# Fri3d_2026_DJ_01.net
KiCad netlist of a schematic drawn in Altium Designer
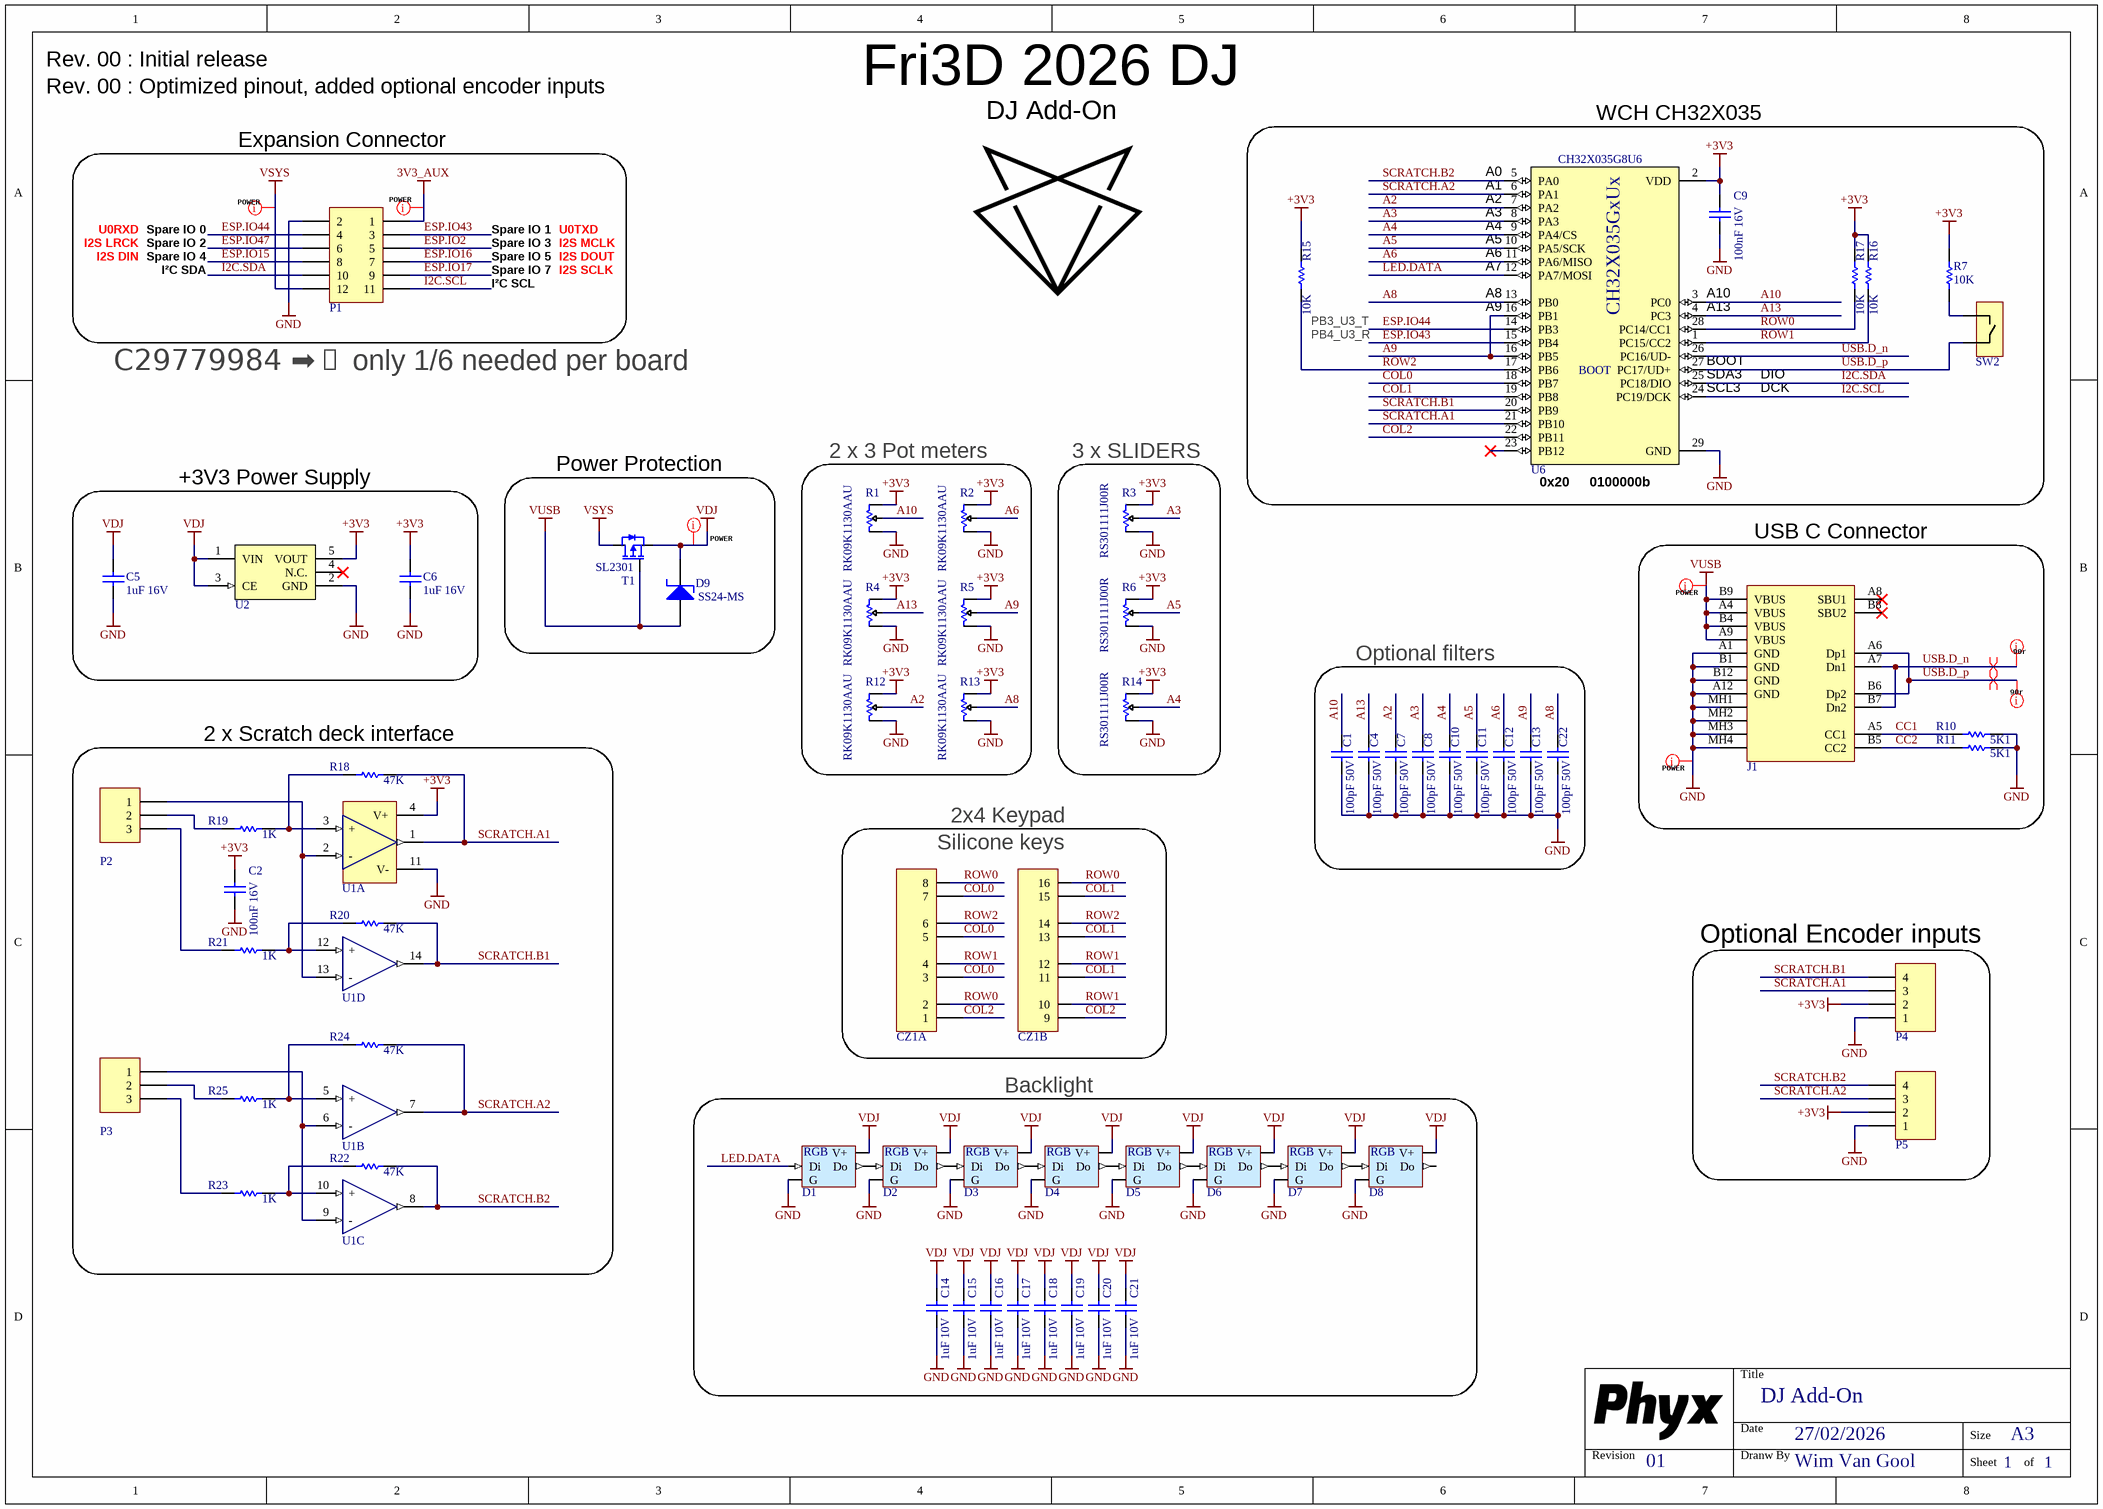
[diagram p0: Fri3d_2026_DJ_01.SchDoc]

(export (version "E")
  (design (tool "Eeschema 10.0.6"))
  (components
    (comp (ref "C1")
      (value "100pF 50V")
      (footprint "C0603_N")
      (description "Capacitor Ceramic")
      (libsource (lib "Phyx_Components") (part "CAP_CERAMIC"))
    )
    (comp (ref "C2")
      (value "100nF 16V")
      (footprint "C0603_N")
      (description "Capacitor Ceramic")
      (libsource (lib "Phyx_Components") (part "CAP_CERAMIC"))
    )
    (comp (ref "C4")
      (value "100pF 50V")
      (footprint "C0603_N")
      (description "Capacitor Ceramic")
      (libsource (lib "Phyx_Components") (part "CAP_CERAMIC"))
    )
    (comp (ref "C5")
      (value "1uF 16V")
      (footprint "C0603_N")
      (description "Capacitor Ceramic")
      (libsource (lib "Phyx_Components") (part "CAP_CERAMIC"))
    )
    (comp (ref "C6")
      (value "1uF 16V")
      (footprint "C0603_N")
      (description "Capacitor Ceramic")
      (libsource (lib "Phyx_Components") (part "CAP_CERAMIC"))
    )
    (comp (ref "C7")
      (value "100pF 50V")
      (footprint "C0603_N")
      (description "Capacitor Ceramic")
      (libsource (lib "Phyx_Components") (part "CAP_CERAMIC"))
    )
    (comp (ref "C8")
      (value "100pF 50V")
      (footprint "C0603_N")
      (description "Capacitor Ceramic")
      (libsource (lib "Phyx_Components") (part "CAP_CERAMIC"))
    )
    (comp (ref "C9")
      (value "100nF 16V")
      (footprint "C0603_N")
      (description "Capacitor Ceramic")
      (libsource (lib "Phyx_Components") (part "CAP_CERAMIC"))
    )
    (comp (ref "C10")
      (value "100pF 50V")
      (footprint "C0603_N")
      (description "Capacitor Ceramic")
      (libsource (lib "Phyx_Components") (part "CAP_CERAMIC"))
    )
    (comp (ref "C11")
      (value "100pF 50V")
      (footprint "C0603_N")
      (description "Capacitor Ceramic")
      (libsource (lib "Phyx_Components") (part "CAP_CERAMIC"))
    )
    (comp (ref "C12")
      (value "100pF 50V")
      (footprint "C0603_N")
      (description "Capacitor Ceramic")
      (libsource (lib "Phyx_Components") (part "CAP_CERAMIC"))
    )
    (comp (ref "C13")
      (value "100pF 50V")
      (footprint "C0603_N")
      (description "Capacitor Ceramic")
      (libsource (lib "Phyx_Components") (part "CAP_CERAMIC"))
    )
    (comp (ref "C14")
      (value "1uF 10V")
      (footprint "C0402")
      (description "Capacitor Ceramic")
      (libsource (lib "Phyx_Components") (part "CAP_CERAMIC"))
    )
    (comp (ref "C15")
      (value "1uF 10V")
      (footprint "C0402")
      (description "Capacitor Ceramic")
      (libsource (lib "Phyx_Components") (part "CAP_CERAMIC"))
    )
    (comp (ref "C16")
      (value "1uF 10V")
      (footprint "C0402")
      (description "Capacitor Ceramic")
      (libsource (lib "Phyx_Components") (part "CAP_CERAMIC"))
    )
    (comp (ref "C17")
      (value "1uF 10V")
      (footprint "C0402")
      (description "Capacitor Ceramic")
      (libsource (lib "Phyx_Components") (part "CAP_CERAMIC"))
    )
    (comp (ref "C18")
      (value "1uF 10V")
      (footprint "C0402")
      (description "Capacitor Ceramic")
      (libsource (lib "Phyx_Components") (part "CAP_CERAMIC"))
    )
    (comp (ref "C19")
      (value "1uF 10V")
      (footprint "C0402")
      (description "Capacitor Ceramic")
      (libsource (lib "Phyx_Components") (part "CAP_CERAMIC"))
    )
    (comp (ref "C20")
      (value "1uF 10V")
      (footprint "C0402")
      (description "Capacitor Ceramic")
      (libsource (lib "Phyx_Components") (part "CAP_CERAMIC"))
    )
    (comp (ref "C21")
      (value "1uF 10V")
      (footprint "C0402")
      (description "Capacitor Ceramic")
      (libsource (lib "Phyx_Components") (part "CAP_CERAMIC"))
    )
    (comp (ref "C22")
      (value "100pF 50V")
      (footprint "C0603_N")
      (description "Capacitor Ceramic")
      (libsource (lib "Phyx_Components") (part "CAP_CERAMIC"))
    )
    (comp (ref "CZ1")
      (value "Campzone 2020 2x4 silicone keypad")
      (footprint "CZ20_2x4")
      (libsource (lib "Phyx_Components") (part "CZ20_2x4"))
    )
    (comp (ref "D1")
      (value "WS2812 based digital RGB LED 5050 White package reduced current")
      (footprint "LED_5050_WS2812B_WHITE")
      (description "=Description")
      (libsource (lib "Phyx_Components") (part "LED_RGB_WS2812B_5050"))
    )
    (comp (ref "D2")
      (value "WS2812 based digital RGB LED 5050 White package reduced current")
      (footprint "LED_5050_WS2812B_WHITE")
      (description "=Description")
      (libsource (lib "Phyx_Components") (part "LED_RGB_WS2812B_5050"))
    )
    (comp (ref "D3")
      (value "WS2812 based digital RGB LED 5050 White package reduced current")
      (footprint "LED_5050_WS2812B_WHITE")
      (description "=Description")
      (libsource (lib "Phyx_Components") (part "LED_RGB_WS2812B_5050"))
    )
    (comp (ref "D4")
      (value "WS2812 based digital RGB LED 5050 White package reduced current")
      (footprint "LED_5050_WS2812B_WHITE")
      (description "=Description")
      (libsource (lib "Phyx_Components") (part "LED_RGB_WS2812B_5050"))
    )
    (comp (ref "D5")
      (value "WS2812 based digital RGB LED 5050 White package reduced current")
      (footprint "LED_5050_WS2812B_WHITE")
      (description "=Description")
      (libsource (lib "Phyx_Components") (part "LED_RGB_WS2812B_5050"))
    )
    (comp (ref "D6")
      (value "WS2812 based digital RGB LED 5050 White package reduced current")
      (footprint "LED_5050_WS2812B_WHITE")
      (description "=Description")
      (libsource (lib "Phyx_Components") (part "LED_RGB_WS2812B_5050"))
    )
    (comp (ref "D7")
      (value "WS2812 based digital RGB LED 5050 White package reduced current")
      (footprint "LED_5050_WS2812B_WHITE")
      (description "=Description")
      (libsource (lib "Phyx_Components") (part "LED_RGB_WS2812B_5050"))
    )
    (comp (ref "D8")
      (value "WS2812 based digital RGB LED 5050 White package reduced current")
      (footprint "LED_5050_WS2812B_WHITE")
      (description "=Description")
      (libsource (lib "Phyx_Components") (part "LED_RGB_WS2812B_5050"))
    )
    (comp (ref "D9")
      (value "SS24-MS")
      (footprint "DO-214AC_AC")
      (description "=Description")
      (fields (field (name "Comment") "40V 2A 550mV@2A DO-214 Schottky"))
      (libsource (lib "Phyx_Components") (part "Schottky_AC"))
    )
    (comp (ref "J1")
      (value "USB 2.0 C Reversible Receptacle Horizontal full SMD")
      (footprint "XUNPU-TYPEC-304S-ACP16")
      (libsource (lib "Phyx_Components") (part "USB_C_16_4"))
    )
    (comp (ref "P1")
      (value "Header 6X2")
      (footprint "HDR2X6")
      (libsource (lib "Phyx_Components") (part "Header 6X2"))
    )
    (comp (ref "P2")
      (value "Header 3")
      (footprint "HDR1X3")
      (libsource (lib "Phyx_Components") (part "Header 3"))
    )
    (comp (ref "P3")
      (value "Header 3")
      (footprint "HDR1X3")
      (libsource (lib "Phyx_Components") (part "Header 3"))
    )
    (comp (ref "P4")
      (value "Header 1.0mm RA Shrouded 4")
      (footprint "WE_665104131822")
      (libsource (lib "Phyx_Components") (part "Header 4"))
    )
    (comp (ref "P5")
      (value "Header 1.0mm RA Shrouded 4")
      (footprint "WE_665104131822")
      (libsource (lib "Phyx_Components") (part "Header 4"))
    )
    (comp (ref "R1")
      (value "RK09K1130AAU")
      (footprint "ALPS_RK09K1130AAU")
      (fields (field (name "Comment") "10kΩ Rotary Potentiometers"))
      (libsource (lib "Phyx_Components") (part "RES_VAR"))
    )
    (comp (ref "R2")
      (value "RK09K1130AAU")
      (footprint "ALPS_RK09K1130AAU")
      (fields (field (name "Comment") "10kΩ Rotary Potentiometers"))
      (libsource (lib "Phyx_Components") (part "RES_VAR"))
    )
    (comp (ref "R3")
      (value "RS301111J00R")
      (footprint "ALPS_RS301111J00R")
      (fields (field (name "Comment") "50kΩ Slide Potentiometers"))
      (libsource (lib "Phyx_Components") (part "RES_VAR"))
    )
    (comp (ref "R4")
      (value "RK09K1130AAU")
      (footprint "ALPS_RK09K1130AAU")
      (fields (field (name "Comment") "10kΩ Rotary Potentiometers"))
      (libsource (lib "Phyx_Components") (part "RES_VAR"))
    )
    (comp (ref "R5")
      (value "RK09K1130AAU")
      (footprint "ALPS_RK09K1130AAU")
      (fields (field (name "Comment") "10kΩ Rotary Potentiometers"))
      (libsource (lib "Phyx_Components") (part "RES_VAR"))
    )
    (comp (ref "R6")
      (value "RS301111J00R")
      (footprint "ALPS_RS301111J00R")
      (fields (field (name "Comment") "50kΩ Slide Potentiometers"))
      (libsource (lib "Phyx_Components") (part "RES_VAR"))
    )
    (comp (ref "R7")
      (value "10K")
      (footprint "R0603_N")
      (libsource (lib "Phyx_Components") (part "RESISTOR"))
    )
    (comp (ref "R10")
      (value "5K1")
      (footprint "R0603_N")
      (libsource (lib "Phyx_Components") (part "RESISTOR"))
    )
    (comp (ref "R11")
      (value "5K1")
      (footprint "R0603_N")
      (libsource (lib "Phyx_Components") (part "RESISTOR"))
    )
    (comp (ref "R12")
      (value "RK09K1130AAU")
      (footprint "ALPS_RK09K1130AAU")
      (fields (field (name "Comment") "10kΩ Rotary Potentiometers"))
      (libsource (lib "Phyx_Components") (part "RES_VAR"))
    )
    (comp (ref "R13")
      (value "RK09K1130AAU")
      (footprint "ALPS_RK09K1130AAU")
      (fields (field (name "Comment") "10kΩ Rotary Potentiometers"))
      (libsource (lib "Phyx_Components") (part "RES_VAR"))
    )
    (comp (ref "R14")
      (value "RS301111J00R")
      (footprint "ALPS_RS301111J00R")
      (fields (field (name "Comment") "50kΩ Slide Potentiometers"))
      (libsource (lib "Phyx_Components") (part "RES_VAR"))
    )
    (comp (ref "R15")
      (value "10K")
      (footprint "R0603_N")
      (libsource (lib "Phyx_Components") (part "RESISTOR"))
    )
    (comp (ref "R16")
      (value "10K")
      (footprint "R0603_N")
      (libsource (lib "Phyx_Components") (part "RESISTOR"))
    )
    (comp (ref "R17")
      (value "10K")
      (footprint "R0603_N")
      (libsource (lib "Phyx_Components") (part "RESISTOR"))
    )
    (comp (ref "R18")
      (value "47K")
      (footprint "R0603_N")
      (fields (field (name "Comment") "RESISTOR"))
      (libsource (lib "Phyx_Components") (part "RESISTOR"))
    )
    (comp (ref "R19")
      (value "1K")
      (footprint "R0603_N")
      (libsource (lib "Phyx_Components") (part "RESISTOR"))
    )
    (comp (ref "R20")
      (value "47K")
      (footprint "R0603_N")
      (fields (field (name "Comment") "RESISTOR"))
      (libsource (lib "Phyx_Components") (part "RESISTOR"))
    )
    (comp (ref "R21")
      (value "1K")
      (footprint "R0603_N")
      (libsource (lib "Phyx_Components") (part "RESISTOR"))
    )
    (comp (ref "R22")
      (value "47K")
      (footprint "R0603_N")
      (fields (field (name "Comment") "RESISTOR"))
      (libsource (lib "Phyx_Components") (part "RESISTOR"))
    )
    (comp (ref "R23")
      (value "1K")
      (footprint "R0603_N")
      (libsource (lib "Phyx_Components") (part "RESISTOR"))
    )
    (comp (ref "R24")
      (value "47K")
      (footprint "R0603_N")
      (fields (field (name "Comment") "RESISTOR"))
      (libsource (lib "Phyx_Components") (part "RESISTOR"))
    )
    (comp (ref "R25")
      (value "1K")
      (footprint "R0603_N")
      (libsource (lib "Phyx_Components") (part "RESISTOR"))
    )
    (comp (ref "SW2")
      (value "4.5x4.5mm tact SMD H3,8mm")
      (footprint "WE_430181038816")
      (libsource (lib "Phyx_Components") (part "SW_TACT"))
    )
    (comp (ref "T1")
      (value "SL2301")
      (footprint "SOT23-3")
      (description "=Description")
      (fields (field (name "Comment") "-2.3A -20V P-Ch MOSFET Vgs -1V"))
      (libsource (lib "Phyx_Components") (part "P_MOSFET_GSD"))
    )
    (comp (ref "U1")
      (value "Quad, 30-V, 1-MHz operational amplifier")
      (footprint "SOIC_N_14")
      (description "=Description")
      (libsource (lib "Phyx_Components") (part "OPA4134"))
    )
    (comp (ref "U2")
      (value "3V3 LDO 300mA 150mV")
      (footprint "SOT23-5")
      (description "=Designator")
      (libsource (lib "Phyx_Components") (part "XC6210_SOT"))
    )
    (comp (ref "U6")
      (value "CH32X035G8U6")
      (footprint "QFN_28_4.0x4.0_P0.4")
      (fields
        (field (name "Comment") "WCH CH32X035G8U6 QFN28 RISC-V 32-bit MCU, 62KB Flash, 10KB RAM, USB PD")
      )
      (libsource (lib "Phyx_Components") (part "WCH_CH32X035GxUx"))
    )
  )
  (nets
    (net (code "1") (name "+3V3") (class "Default")
      (node (ref "C2") (pin "1") (pinfunction "1_1") (pintype "passive"))
      (node (ref "C6") (pin "1") (pinfunction "1_1") (pintype "passive"))
      (node (ref "C9") (pin "1") (pinfunction "1_1") (pintype "passive"))
      (node (ref "P4") (pin "2") (pinfunction "2_2") (pintype "passive"))
      (node (ref "P5") (pin "2") (pinfunction "2_2") (pintype "passive"))
      (node (ref "R1") (pin "1") (pinfunction "1_1") (pintype "passive"))
      (node (ref "R12") (pin "1") (pinfunction "1_1") (pintype "passive"))
      (node (ref "R13") (pin "1") (pinfunction "1_1") (pintype "passive"))
      (node (ref "R14") (pin "1") (pinfunction "1_1") (pintype "passive"))
      (node (ref "R15") (pin "1") (pinfunction "1_1") (pintype "passive"))
      (node (ref "R16") (pin "1") (pinfunction "1_1") (pintype "passive"))
      (node (ref "R17") (pin "1") (pinfunction "1_1") (pintype "passive"))
      (node (ref "R2") (pin "1") (pinfunction "1_1") (pintype "passive"))
      (node (ref "R3") (pin "1") (pinfunction "1_1") (pintype "passive"))
      (node (ref "R4") (pin "1") (pinfunction "1_1") (pintype "passive"))
      (node (ref "R5") (pin "1") (pinfunction "1_1") (pintype "passive"))
      (node (ref "R6") (pin "1") (pinfunction "1_1") (pintype "passive"))
      (node (ref "R7") (pin "1") (pinfunction "1_1") (pintype "passive"))
      (node (ref "U1") (pin "4") (pinfunction "V+_4") (pintype "power_in"))
      (node (ref "U2") (pin "5") (pinfunction "VOUT_5") (pintype "power_in"))
      (node (ref "U6") (pin "2") (pinfunction "VDD_2") (pintype "power_in"))
    )
    (net (code "2") (name "/A2") (class "Default")
      (node (ref "C7") (pin "1") (pinfunction "1_1") (pintype "passive"))
      (node (ref "R12") (pin "2") (pinfunction "2_2") (pintype "passive"))
      (node (ref "U6") (pin "7") (pinfunction "PA2_7") (pintype "bidirectional"))
    )
    (net (code "3") (name "/A3") (class "Default")
      (node (ref "C8") (pin "1") (pinfunction "1_1") (pintype "passive"))
      (node (ref "R3") (pin "2") (pinfunction "2_2") (pintype "passive"))
      (node (ref "U6") (pin "8") (pinfunction "PA3_8") (pintype "bidirectional"))
    )
    (net (code "4") (name "/A4") (class "Default")
      (node (ref "C10") (pin "1") (pinfunction "1_1") (pintype "passive"))
      (node (ref "R14") (pin "2") (pinfunction "2_2") (pintype "passive"))
      (node (ref "U6") (pin "9") (pinfunction "PA4/CS_9") (pintype "bidirectional"))
    )
    (net (code "5") (name "/A5") (class "Default")
      (node (ref "C11") (pin "1") (pinfunction "1_1") (pintype "passive"))
      (node (ref "R6") (pin "2") (pinfunction "2_2") (pintype "passive"))
      (node (ref "U6") (pin "10") (pinfunction "PA5/SCK_10") (pintype "bidirectional"))
    )
    (net (code "6") (name "/A6") (class "Default")
      (node (ref "C12") (pin "1") (pinfunction "1_1") (pintype "passive"))
      (node (ref "R2") (pin "2") (pinfunction "2_2") (pintype "passive"))
      (node (ref "U6") (pin "11") (pinfunction "PA6/MISO_11") (pintype "bidirectional"))
    )
    (net (code "7") (name "/A8") (class "Default")
      (node (ref "C22") (pin "1") (pinfunction "1_1") (pintype "passive"))
      (node (ref "R13") (pin "2") (pinfunction "2_2") (pintype "passive"))
      (node (ref "U6") (pin "13") (pinfunction "PB0_13") (pintype "bidirectional"))
    )
    (net (code "8") (name "/A9") (class "Default")
      (node (ref "C13") (pin "1") (pinfunction "1_1") (pintype "passive"))
      (node (ref "R5") (pin "2") (pinfunction "2_2") (pintype "passive"))
      (node (ref "U6") (pin "16") (pinfunction "PB1_16") (pintype "bidirectional"))
    )
    (net (code "9") (name "/A10") (class "Default")
      (node (ref "C1") (pin "1") (pinfunction "1_1") (pintype "passive"))
      (node (ref "R1") (pin "2") (pinfunction "2_2") (pintype "passive"))
      (node (ref "U6") (pin "3") (pinfunction "PC0_3") (pintype "bidirectional"))
    )
    (net (code "10") (name "/A13") (class "Default")
      (node (ref "C4") (pin "1") (pinfunction "1_1") (pintype "passive"))
      (node (ref "R4") (pin "2") (pinfunction "2_2") (pintype "passive"))
      (node (ref "U6") (pin "4") (pinfunction "PC3_4") (pintype "bidirectional"))
    )
    (net (code "11") (name "/CC1") (class "Default")
      (node (ref "J1") (pin "A5") (pinfunction "CC1_A5") (pintype "passive"))
      (node (ref "R10") (pin "1") (pinfunction "1_1") (pintype "passive"))
    )
    (net (code "12") (name "/CC2") (class "Default")
      (node (ref "J1") (pin "B5") (pinfunction "CC2_B5") (pintype "passive"))
      (node (ref "R11") (pin "1") (pinfunction "1_1") (pintype "passive"))
    )
    (net (code "13") (name "/COL0") (class "Default")
      (node (ref "CZ1") (pin "3") (pinfunction "3_3") (pintype "passive"))
      (node (ref "CZ1") (pin "5") (pinfunction "5_5") (pintype "passive"))
      (node (ref "CZ1") (pin "7") (pinfunction "7_7") (pintype "passive"))
      (node (ref "U6") (pin "18") (pinfunction "PB7_18") (pintype "bidirectional"))
    )
    (net (code "14") (name "/COL1") (class "Default")
      (node (ref "CZ1") (pin "11") (pinfunction "11_11") (pintype "passive"))
      (node (ref "CZ1") (pin "13") (pinfunction "13_13") (pintype "passive"))
      (node (ref "CZ1") (pin "15") (pinfunction "15_15") (pintype "passive"))
      (node (ref "U6") (pin "19") (pinfunction "PB8_19") (pintype "bidirectional"))
    )
    (net (code "15") (name "/COL2") (class "Default")
      (node (ref "CZ1") (pin "1") (pinfunction "1_1") (pintype "passive"))
      (node (ref "CZ1") (pin "9") (pinfunction "9_9") (pintype "passive"))
      (node (ref "U6") (pin "22") (pinfunction "PB11_22") (pintype "bidirectional"))
    )
    (net (code "16") (name "/ESP.IO2") (class "Default")
      (node (ref "P1") (pin "5") (pinfunction "5_5") (pintype "passive"))
    )
    (net (code "17") (name "/ESP.IO15") (class "Default")
      (node (ref "P1") (pin "8") (pinfunction "8_8") (pintype "passive"))
    )
    (net (code "18") (name "/ESP.IO16") (class "Default")
      (node (ref "P1") (pin "7") (pinfunction "7_7") (pintype "passive"))
    )
    (net (code "19") (name "/ESP.IO17") (class "Default")
      (node (ref "P1") (pin "9") (pinfunction "9_9") (pintype "passive"))
    )
    (net (code "20") (name "/ESP.IO43") (class "Default")
      (node (ref "P1") (pin "3") (pinfunction "3_3") (pintype "passive"))
      (node (ref "U6") (pin "15") (pinfunction "PB4_15") (pintype "bidirectional"))
    )
    (net (code "21") (name "/ESP.IO44") (class "Default")
      (node (ref "P1") (pin "4") (pinfunction "4_4") (pintype "passive"))
      (node (ref "U6") (pin "14") (pinfunction "PB3_14") (pintype "bidirectional"))
    )
    (net (code "22") (name "/ESP.IO47") (class "Default")
      (node (ref "P1") (pin "6") (pinfunction "6_6") (pintype "passive"))
    )
    (net (code "23") (name "/I2C.SCL") (class "Default")
      (node (ref "P1") (pin "11") (pinfunction "11_11") (pintype "passive"))
      (node (ref "U6") (pin "24") (pinfunction "PC19/DCK_24") (pintype "bidirectional"))
    )
    (net (code "24") (name "/I2C.SDA") (class "Default")
      (node (ref "P1") (pin "10") (pinfunction "10_10") (pintype "passive"))
      (node (ref "U6") (pin "25") (pinfunction "PC18/DIO_25") (pintype "bidirectional"))
    )
    (net (code "25") (name "/LED.DATA") (class "Default")
      (node (ref "D1") (pin "4") (pinfunction "Di_4") (pintype "input"))
      (node (ref "U6") (pin "12") (pinfunction "PA7/MOSI_12") (pintype "bidirectional"))
    )
    (net (code "26") (name "/ROW0") (class "Default")
      (node (ref "CZ1") (pin "16") (pinfunction "16_16") (pintype "passive"))
      (node (ref "CZ1") (pin "2") (pinfunction "2_2") (pintype "passive"))
      (node (ref "CZ1") (pin "8") (pinfunction "8_8") (pintype "passive"))
      (node (ref "R17") (pin "2") (pinfunction "2_2") (pintype "passive"))
      (node (ref "U6") (pin "28") (pinfunction "PC14/CC1_28") (pintype "bidirectional"))
    )
    (net (code "27") (name "/ROW1") (class "Default")
      (node (ref "CZ1") (pin "10") (pinfunction "10_10") (pintype "passive"))
      (node (ref "CZ1") (pin "12") (pinfunction "12_12") (pintype "passive"))
      (node (ref "CZ1") (pin "4") (pinfunction "4_4") (pintype "passive"))
      (node (ref "R16") (pin "2") (pinfunction "2_2") (pintype "passive"))
      (node (ref "U6") (pin "1") (pinfunction "PC15/CC2_1") (pintype "bidirectional"))
    )
    (net (code "28") (name "/ROW2") (class "Default")
      (node (ref "CZ1") (pin "14") (pinfunction "14_14") (pintype "passive"))
      (node (ref "CZ1") (pin "6") (pinfunction "6_6") (pintype "passive"))
      (node (ref "R15") (pin "2") (pinfunction "2_2") (pintype "passive"))
      (node (ref "U6") (pin "17") (pinfunction "PB6_17") (pintype "bidirectional"))
    )
    (net (code "29") (name "/SCRATCH.A1") (class "Default")
      (node (ref "P4") (pin "3") (pinfunction "3_3") (pintype "passive"))
      (node (ref "R18") (pin "1") (pinfunction "1_1") (pintype "passive"))
      (node (ref "U1") (pin "1") (pinfunction "OUT_1") (pintype "output"))
      (node (ref "U6") (pin "21") (pinfunction "PB10_21") (pintype "bidirectional"))
    )
    (net (code "30") (name "/SCRATCH.A2") (class "Default")
      (node (ref "P5") (pin "3") (pinfunction "3_3") (pintype "passive"))
      (node (ref "R24") (pin "1") (pinfunction "1_1") (pintype "passive"))
      (node (ref "U1") (pin "7") (pinfunction "OUT_7") (pintype "output"))
      (node (ref "U6") (pin "6") (pinfunction "PA1_6") (pintype "bidirectional"))
    )
    (net (code "31") (name "/SCRATCH.B1") (class "Default")
      (node (ref "P4") (pin "4") (pinfunction "4_4") (pintype "passive"))
      (node (ref "R20") (pin "1") (pinfunction "1_1") (pintype "passive"))
      (node (ref "U1") (pin "14") (pinfunction "OUT_14") (pintype "output"))
      (node (ref "U6") (pin "20") (pinfunction "PB9_20") (pintype "bidirectional"))
    )
    (net (code "32") (name "/SCRATCH.B2") (class "Default")
      (node (ref "P5") (pin "4") (pinfunction "4_4") (pintype "passive"))
      (node (ref "R22") (pin "1") (pinfunction "1_1") (pintype "passive"))
      (node (ref "U1") (pin "8") (pinfunction "OUT_8") (pintype "output"))
      (node (ref "U6") (pin "5") (pinfunction "PA0_5") (pintype "bidirectional"))
    )
    (net (code "33") (name "/USB.D_n") (class "Default")
      (node (ref "J1") (pin "A7") (pinfunction "Dn1_A7") (pintype "passive"))
      (node (ref "J1") (pin "B7") (pinfunction "Dn2_B7") (pintype "passive"))
      (node (ref "U6") (pin "26") (pinfunction "PC16/UD-_26") (pintype "bidirectional"))
    )
    (net (code "34") (name "/USB.D_p") (class "Default")
      (node (ref "J1") (pin "A6") (pinfunction "Dp1_A6") (pintype "passive"))
      (node (ref "J1") (pin "B6") (pinfunction "Dp2_B6") (pintype "passive"))
      (node (ref "SW2") (pin "2") (pinfunction "2_2") (pintype "passive"))
      (node (ref "U6") (pin "27") (pinfunction "PC17/UD+_27") (pintype "bidirectional"))
    )
    (net (code "35") (name "3V3_AUX") (class "Default")
      (node (ref "P1") (pin "1") (pinfunction "1_1") (pintype "passive"))
    )
    (net (code "36") (name "GND") (class "Default")
      (node (ref "C1") (pin "2") (pinfunction "2_2") (pintype "passive"))
      (node (ref "C10") (pin "2") (pinfunction "2_2") (pintype "passive"))
      (node (ref "C11") (pin "2") (pinfunction "2_2") (pintype "passive"))
      (node (ref "C12") (pin "2") (pinfunction "2_2") (pintype "passive"))
      (node (ref "C13") (pin "2") (pinfunction "2_2") (pintype "passive"))
      (node (ref "C14") (pin "2") (pinfunction "2_2") (pintype "passive"))
      (node (ref "C15") (pin "2") (pinfunction "2_2") (pintype "passive"))
      (node (ref "C16") (pin "2") (pinfunction "2_2") (pintype "passive"))
      (node (ref "C17") (pin "2") (pinfunction "2_2") (pintype "passive"))
      (node (ref "C18") (pin "2") (pinfunction "2_2") (pintype "passive"))
      (node (ref "C19") (pin "2") (pinfunction "2_2") (pintype "passive"))
      (node (ref "C2") (pin "2") (pinfunction "2_2") (pintype "passive"))
      (node (ref "C20") (pin "2") (pinfunction "2_2") (pintype "passive"))
      (node (ref "C21") (pin "2") (pinfunction "2_2") (pintype "passive"))
      (node (ref "C22") (pin "2") (pinfunction "2_2") (pintype "passive"))
      (node (ref "C4") (pin "2") (pinfunction "2_2") (pintype "passive"))
      (node (ref "C5") (pin "2") (pinfunction "2_2") (pintype "passive"))
      (node (ref "C6") (pin "2") (pinfunction "2_2") (pintype "passive"))
      (node (ref "C7") (pin "2") (pinfunction "2_2") (pintype "passive"))
      (node (ref "C8") (pin "2") (pinfunction "2_2") (pintype "passive"))
      (node (ref "C9") (pin "2") (pinfunction "2_2") (pintype "passive"))
      (node (ref "D1") (pin "3") (pinfunction "G_3") (pintype "power_in"))
      (node (ref "D2") (pin "3") (pinfunction "G_3") (pintype "power_in"))
      (node (ref "D3") (pin "3") (pinfunction "G_3") (pintype "power_in"))
      (node (ref "D4") (pin "3") (pinfunction "G_3") (pintype "power_in"))
      (node (ref "D5") (pin "3") (pinfunction "G_3") (pintype "power_in"))
      (node (ref "D6") (pin "3") (pinfunction "G_3") (pintype "power_in"))
      (node (ref "D7") (pin "3") (pinfunction "G_3") (pintype "power_in"))
      (node (ref "D8") (pin "3") (pinfunction "G_3") (pintype "power_in"))
      (node (ref "J1") (pin "A1") (pinfunction "GND_A1") (pintype "passive"))
      (node (ref "J1") (pin "A12") (pinfunction "GND_A12") (pintype "passive"))
      (node (ref "J1") (pin "B1") (pinfunction "GND_B1") (pintype "passive"))
      (node (ref "J1") (pin "B12") (pinfunction "GND_B12") (pintype "passive"))
      (node (ref "J1") (pin "MH1") (pinfunction "Tab_MH1") (pintype "passive"))
      (node (ref "J1") (pin "MH2") (pinfunction "Tab_MH2") (pintype "passive"))
      (node (ref "J1") (pin "MH3") (pinfunction "Tab_MH3") (pintype "passive"))
      (node (ref "J1") (pin "MH4") (pinfunction "Tab_MH4") (pintype "passive"))
      (node (ref "P1") (pin "2") (pinfunction "2_2") (pintype "passive"))
      (node (ref "P4") (pin "1") (pinfunction "1_1") (pintype "passive"))
      (node (ref "P5") (pin "1") (pinfunction "1_1") (pintype "passive"))
      (node (ref "R1") (pin "3") (pinfunction "3_3") (pintype "passive"))
      (node (ref "R10") (pin "2") (pinfunction "2_2") (pintype "passive"))
      (node (ref "R11") (pin "2") (pinfunction "2_2") (pintype "passive"))
      (node (ref "R12") (pin "3") (pinfunction "3_3") (pintype "passive"))
      (node (ref "R13") (pin "3") (pinfunction "3_3") (pintype "passive"))
      (node (ref "R14") (pin "3") (pinfunction "3_3") (pintype "passive"))
      (node (ref "R2") (pin "3") (pinfunction "3_3") (pintype "passive"))
      (node (ref "R3") (pin "3") (pinfunction "3_3") (pintype "passive"))
      (node (ref "R4") (pin "3") (pinfunction "3_3") (pintype "passive"))
      (node (ref "R5") (pin "3") (pinfunction "3_3") (pintype "passive"))
      (node (ref "R6") (pin "3") (pinfunction "3_3") (pintype "passive"))
      (node (ref "U1") (pin "11") (pinfunction "V-_11") (pintype "power_in"))
      (node (ref "U2") (pin "2") (pinfunction "GND_2") (pintype "power_in"))
      (node (ref "U6") (pin "29") (pinfunction "GND_29") (pintype "power_in"))
    )
    (net (code "37") (name "Net-(D1-Do)") (class "Default")
      (node (ref "D1") (pin "2") (pinfunction "Do_2") (pintype "output"))
      (node (ref "D2") (pin "4") (pinfunction "Di_4") (pintype "input"))
    )
    (net (code "38") (name "Net-(D2-Do)") (class "Default")
      (node (ref "D2") (pin "2") (pinfunction "Do_2") (pintype "output"))
      (node (ref "D3") (pin "4") (pinfunction "Di_4") (pintype "input"))
    )
    (net (code "39") (name "Net-(D3-Do)") (class "Default")
      (node (ref "D3") (pin "2") (pinfunction "Do_2") (pintype "output"))
      (node (ref "D4") (pin "4") (pinfunction "Di_4") (pintype "input"))
    )
    (net (code "40") (name "Net-(D4-Do)") (class "Default")
      (node (ref "D4") (pin "2") (pinfunction "Do_2") (pintype "output"))
      (node (ref "D5") (pin "4") (pinfunction "Di_4") (pintype "input"))
    )
    (net (code "41") (name "Net-(D5-Do)") (class "Default")
      (node (ref "D5") (pin "2") (pinfunction "Do_2") (pintype "output"))
      (node (ref "D6") (pin "4") (pinfunction "Di_4") (pintype "input"))
    )
    (net (code "42") (name "Net-(D6-Do)") (class "Default")
      (node (ref "D6") (pin "2") (pinfunction "Do_2") (pintype "output"))
      (node (ref "D7") (pin "4") (pinfunction "Di_4") (pintype "input"))
    )
    (net (code "43") (name "Net-(D7-Do)") (class "Default")
      (node (ref "D7") (pin "2") (pinfunction "Do_2") (pintype "output"))
      (node (ref "D8") (pin "4") (pinfunction "Di_4") (pintype "input"))
    )
    (net (code "44") (name "Net-(P2-Pad2)") (class "Default")
      (node (ref "P2") (pin "2") (pinfunction "2_2") (pintype "passive"))
      (node (ref "R19") (pin "2") (pinfunction "2_2") (pintype "passive"))
    )
    (net (code "45") (name "Net-(P2-Pad3)") (class "Default")
      (node (ref "P2") (pin "3") (pinfunction "3_3") (pintype "passive"))
      (node (ref "R21") (pin "2") (pinfunction "2_2") (pintype "passive"))
    )
    (net (code "46") (name "Net-(P3-Pad2)") (class "Default")
      (node (ref "P3") (pin "2") (pinfunction "2_2") (pintype "passive"))
      (node (ref "R25") (pin "2") (pinfunction "2_2") (pintype "passive"))
    )
    (net (code "47") (name "Net-(P3-Pad3)") (class "Default")
      (node (ref "P3") (pin "3") (pinfunction "3_3") (pintype "passive"))
      (node (ref "R23") (pin "2") (pinfunction "2_2") (pintype "passive"))
    )
    (net (code "48") (name "Net-(R7-Pad2)") (class "Default")
      (node (ref "R7") (pin "2") (pinfunction "2_2") (pintype "passive"))
      (node (ref "SW2") (pin "1") (pinfunction "1_1") (pintype "passive"))
    )
    (net (code "49") (name "Net-(U1A-+)") (class "Default")
      (node (ref "R18") (pin "2") (pinfunction "2_2") (pintype "passive"))
      (node (ref "R19") (pin "1") (pinfunction "1_1") (pintype "passive"))
      (node (ref "U1") (pin "3") (pinfunction "+_3") (pintype "input"))
    )
    (net (code "50") (name "Net-(U1A--)") (class "Default")
      (node (ref "P2") (pin "1") (pinfunction "1_1") (pintype "passive"))
      (node (ref "U1") (pin "13") (pinfunction "-_13") (pintype "input"))
      (node (ref "U1") (pin "2") (pinfunction "-_2") (pintype "input"))
    )
    (net (code "51") (name "Net-(U1B-+)") (class "Default")
      (node (ref "R24") (pin "2") (pinfunction "2_2") (pintype "passive"))
      (node (ref "R25") (pin "1") (pinfunction "1_1") (pintype "passive"))
      (node (ref "U1") (pin "5") (pinfunction "+_5") (pintype "input"))
    )
    (net (code "52") (name "Net-(U1B--)") (class "Default")
      (node (ref "P3") (pin "1") (pinfunction "1_1") (pintype "passive"))
      (node (ref "U1") (pin "6") (pinfunction "-_6") (pintype "input"))
      (node (ref "U1") (pin "9") (pinfunction "-_9") (pintype "input"))
    )
    (net (code "53") (name "Net-(U1C-+)") (class "Default")
      (node (ref "R22") (pin "2") (pinfunction "2_2") (pintype "passive"))
      (node (ref "R23") (pin "1") (pinfunction "1_1") (pintype "passive"))
      (node (ref "U1") (pin "10") (pinfunction "+_10") (pintype "input"))
    )
    (net (code "54") (name "Net-(U1D-+)") (class "Default")
      (node (ref "R20") (pin "2") (pinfunction "2_2") (pintype "passive"))
      (node (ref "R21") (pin "1") (pinfunction "1_1") (pintype "passive"))
      (node (ref "U1") (pin "12") (pinfunction "+_12") (pintype "input"))
    )
    (net (code "55") (name "VDJ") (class "Default")
      (node (ref "C14") (pin "1") (pinfunction "1_1") (pintype "passive"))
      (node (ref "C15") (pin "1") (pinfunction "1_1") (pintype "passive"))
      (node (ref "C16") (pin "1") (pinfunction "1_1") (pintype "passive"))
      (node (ref "C17") (pin "1") (pinfunction "1_1") (pintype "passive"))
      (node (ref "C18") (pin "1") (pinfunction "1_1") (pintype "passive"))
      (node (ref "C19") (pin "1") (pinfunction "1_1") (pintype "passive"))
      (node (ref "C20") (pin "1") (pinfunction "1_1") (pintype "passive"))
      (node (ref "C21") (pin "1") (pinfunction "1_1") (pintype "passive"))
      (node (ref "C5") (pin "1") (pinfunction "1_1") (pintype "passive"))
      (node (ref "D1") (pin "1") (pinfunction "V+_1") (pintype "power_in"))
      (node (ref "D2") (pin "1") (pinfunction "V+_1") (pintype "power_in"))
      (node (ref "D3") (pin "1") (pinfunction "V+_1") (pintype "power_in"))
      (node (ref "D4") (pin "1") (pinfunction "V+_1") (pintype "power_in"))
      (node (ref "D5") (pin "1") (pinfunction "V+_1") (pintype "power_in"))
      (node (ref "D6") (pin "1") (pinfunction "V+_1") (pintype "power_in"))
      (node (ref "D7") (pin "1") (pinfunction "V+_1") (pintype "power_in"))
      (node (ref "D8") (pin "1") (pinfunction "V+_1") (pintype "power_in"))
      (node (ref "D9") (pin "C") (pinfunction "C_C") (pintype "passive"))
      (node (ref "T1") (pin "2") (pinfunction "S_2") (pintype "passive"))
      (node (ref "U2") (pin "1") (pinfunction "VIN_1") (pintype "power_in"))
      (node (ref "U2") (pin "3") (pinfunction "CE_3") (pintype "input"))
    )
    (net (code "56") (name "VSYS") (class "Default")
      (node (ref "P1") (pin "12") (pinfunction "12_12") (pintype "passive"))
      (node (ref "T1") (pin "3") (pinfunction "D_3") (pintype "passive"))
    )
    (net (code "57") (name "VUSB") (class "Default")
      (node (ref "D9") (pin "A") (pinfunction "A_A") (pintype "passive"))
      (node (ref "J1") (pin "A4") (pinfunction "VBUS_A4") (pintype "passive"))
      (node (ref "J1") (pin "A9") (pinfunction "VBUS_A9") (pintype "passive"))
      (node (ref "J1") (pin "B4") (pinfunction "VBUS_B4") (pintype "passive"))
      (node (ref "J1") (pin "B9") (pinfunction "VBUS_B9") (pintype "passive"))
      (node (ref "T1") (pin "1") (pinfunction "G_1") (pintype "passive"))
    )
    (net (code "58") (name "unconnected-(D8-Do-Pad2)") (class "Default")
      (node (ref "D8") (pin "2") (pinfunction "Do_2") (pintype "output"))
    )
    (net (code "59") (name "unconnected-(J1-SBU1-PadA8)") (class "Default")
      (node (ref "J1") (pin "A8") (pinfunction "SBU1_A8") (pintype "passive+no_connect"))
    )
    (net (code "60") (name "unconnected-(J1-SBU2-PadB8)") (class "Default")
      (node (ref "J1") (pin "B8") (pinfunction "SBU2_B8") (pintype "passive+no_connect"))
    )
    (net (code "61") (name "unconnected-(U2-N.C.-Pad4)") (class "Default")
      (node (ref "U2") (pin "4") (pinfunction "N.C._4") (pintype "passive+no_connect"))
    )
    (net (code "62") (name "unconnected-(U6-PB12-Pad23)") (class "Default")
      (node (ref "U6") (pin "23") (pinfunction "PB12_23") (pintype "bidirectional+no_connect"))
    )
  )
)
